# nano-shieldv4.net
KiCad netlist of a schematic drawn in EAGLE
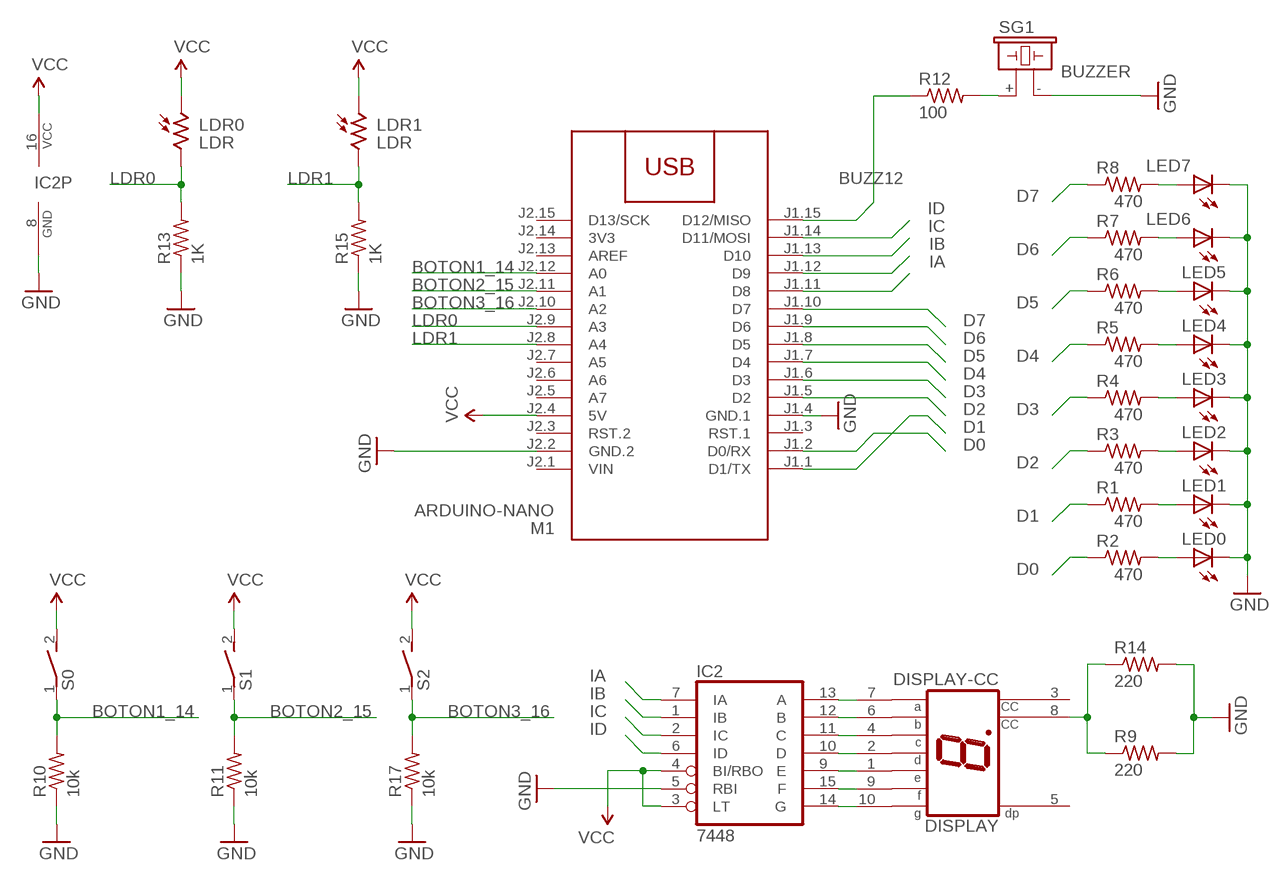
[diagram p0: schematic, sheet 1]

(export (version "E")
  (design (tool "Eeschema 10.0.6"))
  (components
    (comp (ref "DISPLAY")
      (value "DISPLAY-CC")
      (footprint "eagle-import:HDSP-M")
      (libsource (lib "eagle-import") (part "HD-H103"))
    )
    (comp (ref "IC2")
      (value "7448")
      (footprint "eagle-import:DIL16")
      (libsource (lib "eagle-import") (part "7448NLS"))
    )
    (comp (ref "LDR0")
      (value "LDR")
      (footprint "eagle-import:TO46-VT200")
      (libsource (lib "eagle-import") (part "VT20N1"))
    )
    (comp (ref "LDR1")
      (value "LDR")
      (footprint "eagle-import:TO46-VT200")
      (libsource (lib "eagle-import") (part "VT20N1"))
    )
    (comp (ref "LED0")
      (value "LED5MM")
      (footprint "eagle-import:LED5MM")
      (libsource (lib "eagle-import") (part "LED5MM"))
    )
    (comp (ref "LED1")
      (value "LED5MM")
      (footprint "eagle-import:LED5MM")
      (libsource (lib "eagle-import") (part "LED5MM"))
    )
    (comp (ref "LED2")
      (value "LED5MM")
      (footprint "eagle-import:LED5MM")
      (libsource (lib "eagle-import") (part "LED5MM"))
    )
    (comp (ref "LED3")
      (value "LED5MM")
      (footprint "eagle-import:LED5MM")
      (libsource (lib "eagle-import") (part "LED5MM"))
    )
    (comp (ref "LED4")
      (value "LED5MM")
      (footprint "eagle-import:LED5MM")
      (libsource (lib "eagle-import") (part "LED5MM"))
    )
    (comp (ref "LED5")
      (value "LED5MM")
      (footprint "eagle-import:LED5MM")
      (libsource (lib "eagle-import") (part "LED5MM"))
    )
    (comp (ref "LED6")
      (value "LED5MM")
      (footprint "eagle-import:LED5MM")
      (libsource (lib "eagle-import") (part "LED5MM"))
    )
    (comp (ref "LED7")
      (value "LED5MM")
      (footprint "eagle-import:LED5MM")
      (libsource (lib "eagle-import") (part "LED5MM"))
    )
    (comp (ref "M1")
      (value "ARDUINO-NANO")
      (footprint "eagle-import:ARDUINO-NANO-3.0")
      (libsource (lib "eagle-import") (part "ARDUINO-NANO-3.0"))
    )
    (comp (ref "R1")
      (value "470")
      (footprint "eagle-import:0207_10")
      (libsource (lib "eagle-import") (part "R-US_0207/10"))
    )
    (comp (ref "R2")
      (value "470")
      (footprint "eagle-import:0207_10")
      (libsource (lib "eagle-import") (part "R-US_0207/10"))
    )
    (comp (ref "R3")
      (value "470")
      (footprint "eagle-import:0207_10")
      (libsource (lib "eagle-import") (part "R-US_0207/10"))
    )
    (comp (ref "R4")
      (value "470")
      (footprint "eagle-import:0207_10")
      (libsource (lib "eagle-import") (part "R-US_0207/10"))
    )
    (comp (ref "R5")
      (value "470")
      (footprint "eagle-import:0207_10")
      (libsource (lib "eagle-import") (part "R-US_0207/10"))
    )
    (comp (ref "R6")
      (value "470")
      (footprint "eagle-import:0207_10")
      (libsource (lib "eagle-import") (part "R-US_0207/10"))
    )
    (comp (ref "R7")
      (value "470")
      (footprint "eagle-import:0207_10")
      (libsource (lib "eagle-import") (part "R-US_0207/10"))
    )
    (comp (ref "R8")
      (value "470")
      (footprint "eagle-import:0207_10")
      (libsource (lib "eagle-import") (part "R-US_0207/10"))
    )
    (comp (ref "R9")
      (value "220")
      (footprint "eagle-import:0207_10")
      (libsource (lib "eagle-import") (part "R-US_0207/10"))
    )
    (comp (ref "R10")
      (value "10k")
      (footprint "eagle-import:0207_10")
      (libsource (lib "eagle-import") (part "R-US_0207/10"))
    )
    (comp (ref "R11")
      (value "10k")
      (footprint "eagle-import:0207_10")
      (libsource (lib "eagle-import") (part "R-US_0207/10"))
    )
    (comp (ref "R12")
      (value "100")
      (footprint "eagle-import:0207_10")
      (libsource (lib "eagle-import") (part "R-US_0207/10"))
    )
    (comp (ref "R13")
      (value "1K")
      (footprint "eagle-import:0207_10")
      (libsource (lib "eagle-import") (part "R-US_0207/10"))
    )
    (comp (ref "R14")
      (value "220")
      (footprint "eagle-import:0207_10")
      (libsource (lib "eagle-import") (part "R-US_0207/10"))
    )
    (comp (ref "R15")
      (value "1K")
      (footprint "eagle-import:0207_10")
      (libsource (lib "eagle-import") (part "R-US_0207/10"))
    )
    (comp (ref "R17")
      (value "10k")
      (footprint "eagle-import:0207_10")
      (libsource (lib "eagle-import") (part "R-US_0207/10"))
    )
    (comp (ref "S0")
      (value "DS01E")
      (footprint "eagle-import:DS-01")
      (libsource (lib "eagle-import") (part "DS01E"))
    )
    (comp (ref "S1")
      (value "DS01E")
      (footprint "eagle-import:DS-01")
      (libsource (lib "eagle-import") (part "DS01E"))
    )
    (comp (ref "S2")
      (value "DS01E")
      (footprint "eagle-import:DS-01")
      (libsource (lib "eagle-import") (part "DS01E"))
    )
    (comp (ref "SG1")
      (value "BUZZER")
      (footprint "eagle-import:F_CM12P")
      (libsource (lib "eagle-import") (part "F/CM12P"))
    )
  )
  (nets
    (net (code "1") (name "/3V3") (class "Default")
      (node (ref "M1") (pin "J2.14") (pinfunction "3V3_J2.14") (pintype "power_in"))
    )
    (net (code "2") (name "/BOTON1_14") (class "Default")
      (node (ref "M1") (pin "J2.12") (pinfunction "A0_J2.12") (pintype "bidirectional"))
      (node (ref "R10") (pin "2") (pinfunction "2_2") (pintype "passive"))
      (node (ref "S0") (pin "1") (pinfunction "1_1") (pintype "passive"))
    )
    (net (code "3") (name "/BOTON2_15") (class "Default")
      (node (ref "M1") (pin "J2.11") (pinfunction "A1_J2.11") (pintype "bidirectional"))
      (node (ref "R11") (pin "2") (pinfunction "2_2") (pintype "passive"))
      (node (ref "S1") (pin "1") (pinfunction "1_1") (pintype "passive"))
    )
    (net (code "4") (name "/BOTON3_16") (class "Default")
      (node (ref "M1") (pin "J2.10") (pinfunction "A2_J2.10") (pintype "bidirectional"))
      (node (ref "R17") (pin "2") (pinfunction "2_2") (pintype "passive"))
      (node (ref "S2") (pin "1") (pinfunction "1_1") (pintype "passive"))
    )
    (net (code "5") (name "/BUZZ12") (class "Default")
      (node (ref "M1") (pin "J1.15") (pinfunction "D12/MISO_J1.15") (pintype "bidirectional"))
      (node (ref "R12") (pin "1") (pinfunction "1_1") (pintype "passive"))
    )
    (net (code "6") (name "/D0") (class "Default")
      (node (ref "M1") (pin "J1.2") (pinfunction "D0/RX_J1.2") (pintype "bidirectional"))
      (node (ref "R2") (pin "1") (pinfunction "1_1") (pintype "passive"))
    )
    (net (code "7") (name "/D1") (class "Default")
      (node (ref "M1") (pin "J1.1") (pinfunction "D1/TX_J1.1") (pintype "bidirectional"))
      (node (ref "R1") (pin "1") (pinfunction "1_1") (pintype "passive"))
    )
    (net (code "8") (name "/D2") (class "Default")
      (node (ref "M1") (pin "J1.5") (pinfunction "D2_J1.5") (pintype "bidirectional"))
      (node (ref "R3") (pin "1") (pinfunction "1_1") (pintype "passive"))
    )
    (net (code "9") (name "/D3") (class "Default")
      (node (ref "M1") (pin "J1.6") (pinfunction "D3_J1.6") (pintype "bidirectional"))
      (node (ref "R4") (pin "1") (pinfunction "1_1") (pintype "passive"))
    )
    (net (code "10") (name "/D4") (class "Default")
      (node (ref "M1") (pin "J1.7") (pinfunction "D4_J1.7") (pintype "bidirectional"))
      (node (ref "R5") (pin "1") (pinfunction "1_1") (pintype "passive"))
    )
    (net (code "11") (name "/D5") (class "Default")
      (node (ref "M1") (pin "J1.8") (pinfunction "D5_J1.8") (pintype "bidirectional"))
      (node (ref "R6") (pin "1") (pinfunction "1_1") (pintype "passive"))
    )
    (net (code "12") (name "/D6") (class "Default")
      (node (ref "M1") (pin "J1.9") (pinfunction "D6_J1.9") (pintype "bidirectional"))
      (node (ref "R7") (pin "1") (pinfunction "1_1") (pintype "passive"))
    )
    (net (code "13") (name "/D7") (class "Default")
      (node (ref "M1") (pin "J1.10") (pinfunction "D7_J1.10") (pintype "bidirectional"))
      (node (ref "R8") (pin "1") (pinfunction "1_1") (pintype "passive"))
    )
    (net (code "14") (name "/IA") (class "Default")
      (node (ref "IC2") (pin "7") (pinfunction "IA_7") (pintype "input"))
      (node (ref "M1") (pin "J1.11") (pinfunction "D8_J1.11") (pintype "bidirectional"))
    )
    (net (code "15") (name "/IB") (class "Default")
      (node (ref "IC2") (pin "1") (pinfunction "IB_1") (pintype "input"))
      (node (ref "M1") (pin "J1.12") (pinfunction "D9_J1.12") (pintype "bidirectional"))
    )
    (net (code "16") (name "/IC") (class "Default")
      (node (ref "IC2") (pin "2") (pinfunction "IC_2") (pintype "input"))
      (node (ref "M1") (pin "J1.13") (pinfunction "D10_J1.13") (pintype "bidirectional"))
    )
    (net (code "17") (name "/ID") (class "Default")
      (node (ref "IC2") (pin "6") (pinfunction "ID_6") (pintype "input"))
      (node (ref "M1") (pin "J1.14") (pinfunction "D11/MOSI_J1.14") (pintype "bidirectional"))
    )
    (net (code "18") (name "/LDR0") (class "Default")
      (node (ref "LDR0") (pin "2") (pinfunction "2_2") (pintype "passive"))
      (node (ref "M1") (pin "J2.9") (pinfunction "A3_J2.9") (pintype "bidirectional"))
      (node (ref "R13") (pin "2") (pinfunction "2_2") (pintype "passive"))
    )
    (net (code "19") (name "/LDR1") (class "Default")
      (node (ref "LDR1") (pin "2") (pinfunction "2_2") (pintype "passive"))
      (node (ref "M1") (pin "J2.8") (pinfunction "A4_J2.8") (pintype "bidirectional"))
      (node (ref "R15") (pin "2") (pinfunction "2_2") (pintype "passive"))
    )
    (net (code "20") (name "/VIN") (class "Default")
      (node (ref "M1") (pin "J2.1") (pinfunction "VIN_J2.1") (pintype "power_in"))
    )
    (net (code "21") (name "GND") (class "Default")
      (node (ref "IC2") (pin "5") (pinfunction "RBI_5") (pintype "input"))
      (node (ref "IC2") (pin "8") (pinfunction "GND_8") (pintype "power_in"))
      (node (ref "LED0") (pin "K") (pinfunction "C_K") (pintype "passive"))
      (node (ref "LED1") (pin "K") (pinfunction "C_K") (pintype "passive"))
      (node (ref "LED2") (pin "K") (pinfunction "C_K") (pintype "passive"))
      (node (ref "LED3") (pin "K") (pinfunction "C_K") (pintype "passive"))
      (node (ref "LED4") (pin "K") (pinfunction "C_K") (pintype "passive"))
      (node (ref "LED5") (pin "K") (pinfunction "C_K") (pintype "passive"))
      (node (ref "LED6") (pin "K") (pinfunction "C_K") (pintype "passive"))
      (node (ref "LED7") (pin "K") (pinfunction "C_K") (pintype "passive"))
      (node (ref "M1") (pin "J1.4") (pinfunction "GND.1_J1.4") (pintype "power_in"))
      (node (ref "M1") (pin "J2.2") (pinfunction "GND.2_J2.2") (pintype "power_in"))
      (node (ref "R10") (pin "1") (pinfunction "1_1") (pintype "passive"))
      (node (ref "R11") (pin "1") (pinfunction "1_1") (pintype "passive"))
      (node (ref "R13") (pin "1") (pinfunction "1_1") (pintype "passive"))
      (node (ref "R14") (pin "2") (pinfunction "2_2") (pintype "passive"))
      (node (ref "R15") (pin "1") (pinfunction "1_1") (pintype "passive"))
      (node (ref "R17") (pin "1") (pinfunction "1_1") (pintype "passive"))
      (node (ref "R9") (pin "2") (pinfunction "2_2") (pintype "passive"))
      (node (ref "SG1") (pin "-") (pinfunction "2_-") (pintype "passive"))
    )
    (net (code "22") (name "Net-(DISPLAY-A)") (class "Default")
      (node (ref "DISPLAY") (pin "7") (pinfunction "A_7") (pintype "passive"))
      (node (ref "IC2") (pin "13") (pinfunction "A_13") (pintype "output"))
    )
    (net (code "23") (name "Net-(DISPLAY-B)") (class "Default")
      (node (ref "DISPLAY") (pin "6") (pinfunction "B_6") (pintype "passive"))
      (node (ref "IC2") (pin "12") (pinfunction "B_12") (pintype "output"))
    )
    (net (code "24") (name "Net-(DISPLAY-C)") (class "Default")
      (node (ref "DISPLAY") (pin "4") (pinfunction "C_4") (pintype "passive"))
      (node (ref "IC2") (pin "11") (pinfunction "C_11") (pintype "output"))
    )
    (net (code "25") (name "Net-(DISPLAY-CC-Pad8)") (class "Default")
      (node (ref "DISPLAY") (pin "8") (pinfunction "CC_8") (pintype "passive"))
      (node (ref "R14") (pin "1") (pinfunction "1_1") (pintype "passive"))
      (node (ref "R9") (pin "1") (pinfunction "1_1") (pintype "passive"))
    )
    (net (code "26") (name "Net-(DISPLAY-D)") (class "Default")
      (node (ref "DISPLAY") (pin "2") (pinfunction "D_2") (pintype "passive"))
      (node (ref "IC2") (pin "10") (pinfunction "D_10") (pintype "output"))
    )
    (net (code "27") (name "Net-(DISPLAY-E)") (class "Default")
      (node (ref "DISPLAY") (pin "1") (pinfunction "E_1") (pintype "passive"))
      (node (ref "IC2") (pin "9") (pinfunction "E_9") (pintype "output"))
    )
    (net (code "28") (name "Net-(DISPLAY-F)") (class "Default")
      (node (ref "DISPLAY") (pin "9") (pinfunction "F_9") (pintype "passive"))
      (node (ref "IC2") (pin "15") (pinfunction "F_15") (pintype "output"))
    )
    (net (code "29") (name "Net-(DISPLAY-G)") (class "Default")
      (node (ref "DISPLAY") (pin "10") (pinfunction "G_10") (pintype "passive"))
      (node (ref "IC2") (pin "14") (pinfunction "G_14") (pintype "output"))
    )
    (net (code "30") (name "Net-(LED0-PadA)") (class "Default")
      (node (ref "LED0") (pin "A") (pinfunction "A_A") (pintype "passive"))
      (node (ref "R2") (pin "2") (pinfunction "2_2") (pintype "passive"))
    )
    (net (code "31") (name "Net-(LED1-PadA)") (class "Default")
      (node (ref "LED1") (pin "A") (pinfunction "A_A") (pintype "passive"))
      (node (ref "R1") (pin "2") (pinfunction "2_2") (pintype "passive"))
    )
    (net (code "32") (name "Net-(LED2-PadA)") (class "Default")
      (node (ref "LED2") (pin "A") (pinfunction "A_A") (pintype "passive"))
      (node (ref "R3") (pin "2") (pinfunction "2_2") (pintype "passive"))
    )
    (net (code "33") (name "Net-(LED3-PadA)") (class "Default")
      (node (ref "LED3") (pin "A") (pinfunction "A_A") (pintype "passive"))
      (node (ref "R4") (pin "2") (pinfunction "2_2") (pintype "passive"))
    )
    (net (code "34") (name "Net-(LED4-PadA)") (class "Default")
      (node (ref "LED4") (pin "A") (pinfunction "A_A") (pintype "passive"))
      (node (ref "R5") (pin "2") (pinfunction "2_2") (pintype "passive"))
    )
    (net (code "35") (name "Net-(LED5-PadA)") (class "Default")
      (node (ref "LED5") (pin "A") (pinfunction "A_A") (pintype "passive"))
      (node (ref "R6") (pin "2") (pinfunction "2_2") (pintype "passive"))
    )
    (net (code "36") (name "Net-(LED6-PadA)") (class "Default")
      (node (ref "LED6") (pin "A") (pinfunction "A_A") (pintype "passive"))
      (node (ref "R7") (pin "2") (pinfunction "2_2") (pintype "passive"))
    )
    (net (code "37") (name "Net-(LED7-PadA)") (class "Default")
      (node (ref "LED7") (pin "A") (pinfunction "A_A") (pintype "passive"))
      (node (ref "R8") (pin "2") (pinfunction "2_2") (pintype "passive"))
    )
    (net (code "38") (name "Net-(SG1-1)") (class "Default")
      (node (ref "R12") (pin "2") (pinfunction "2_2") (pintype "passive"))
      (node (ref "SG1") (pin "+") (pinfunction "1_+") (pintype "passive"))
    )
    (net (code "39") (name "VCC") (class "Default")
      (node (ref "IC2") (pin "16") (pinfunction "VCC_16") (pintype "power_in"))
      (node (ref "IC2") (pin "3") (pinfunction "LT_3") (pintype "input"))
      (node (ref "IC2") (pin "4") (pinfunction "BI/RBO_4") (pintype "input"))
      (node (ref "LDR0") (pin "1") (pinfunction "1_1") (pintype "passive"))
      (node (ref "LDR1") (pin "1") (pinfunction "1_1") (pintype "passive"))
      (node (ref "M1") (pin "J2.4") (pinfunction "5V_J2.4") (pintype "power_in"))
      (node (ref "S0") (pin "2") (pinfunction "2_2") (pintype "passive"))
      (node (ref "S1") (pin "2") (pinfunction "2_2") (pintype "passive"))
      (node (ref "S2") (pin "2") (pinfunction "2_2") (pintype "passive"))
    )
    (net (code "40") (name "unconnected-(DISPLAY-CC-Pad3)") (class "Default")
      (node (ref "DISPLAY") (pin "3") (pinfunction "CC_3") (pintype "passive"))
    )
    (net (code "41") (name "unconnected-(DISPLAY-DP-Pad5)") (class "Default")
      (node (ref "DISPLAY") (pin "5") (pinfunction "DP_5") (pintype "passive"))
    )
    (net (code "42") (name "unconnected-(M1-A5-PadJ2.7)") (class "Default")
      (node (ref "M1") (pin "J2.7") (pinfunction "A5_J2.7") (pintype "bidirectional"))
    )
    (net (code "43") (name "unconnected-(M1-A6-PadJ2.6)") (class "Default")
      (node (ref "M1") (pin "J2.6") (pinfunction "A6_J2.6") (pintype "bidirectional"))
    )
    (net (code "44") (name "unconnected-(M1-A7-PadJ2.5)") (class "Default")
      (node (ref "M1") (pin "J2.5") (pinfunction "A7_J2.5") (pintype "bidirectional"))
    )
    (net (code "45") (name "unconnected-(M1-AREF-PadJ2.13)") (class "Default")
      (node (ref "M1") (pin "J2.13") (pinfunction "AREF_J2.13") (pintype "bidirectional"))
    )
    (net (code "46") (name "unconnected-(M1-D13{slash}SCK-PadJ2.15)") (class "Default")
      (node (ref "M1") (pin "J2.15") (pinfunction "D13/SCK_J2.15") (pintype "bidirectional"))
    )
    (net (code "47") (name "unconnected-(M1-RST.1-PadJ1.3)") (class "Default")
      (node (ref "M1") (pin "J1.3") (pinfunction "RST.1_J1.3") (pintype "bidirectional"))
    )
    (net (code "48") (name "unconnected-(M1-RST.2-PadJ2.3)") (class "Default")
      (node (ref "M1") (pin "J2.3") (pinfunction "RST.2_J2.3") (pintype "bidirectional"))
    )
  )
)
